# RFM_Sockel.net
KiCad netlist of a schematic drawn in EAGLE
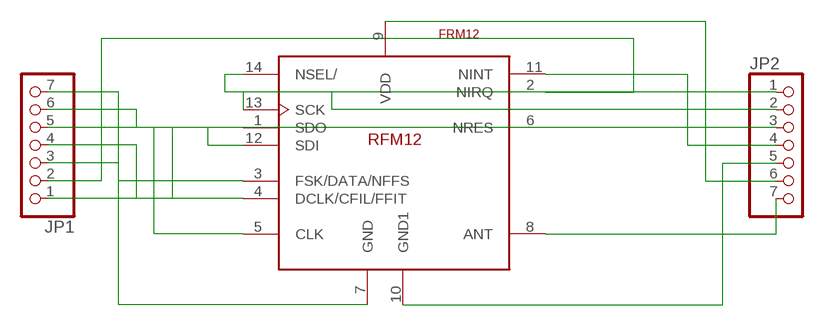
[diagram p0: schematic, sheet 1]

(export (version "E")
  (design (tool "Eeschema 10.0.6"))
  (components
    (comp (ref "JP1")
      (value "PINHD-1X7")
      (footprint "eagle-import:1X07")
      (libsource (lib "eagle-import") (part "PINHD-1X7"))
    )
    (comp (ref "JP2")
      (value "PINHD-1X7")
      (footprint "eagle-import:1X07")
      (libsource (lib "eagle-import") (part "PINHD-1X7"))
    )
    (comp (ref "U$1")
      (value "FRM12")
      (footprint "eagle-import:RFM12")
      (libsource (lib "eagle-import") (part "FRM12"))
    )
  )
  (nets
    (net (code "1") (name "Net-(U$1-ANT)") (class "Default")
      (node (ref "JP2") (pin "7") (pinfunction "7_7") (pintype "passive"))
      (node (ref "U$1") (pin "8") (pinfunction "ANT_8") (pintype "bidirectional"))
    )
    (net (code "2") (name "Net-(U$1-CLK)") (class "Default")
      (node (ref "JP1") (pin "5") (pinfunction "5_5") (pintype "passive"))
      (node (ref "U$1") (pin "5") (pinfunction "CLK_5") (pintype "output"))
    )
    (net (code "3") (name "Net-(U$1-DCLK{slash}CFIL{slash}FFIT)") (class "Default")
      (node (ref "JP1") (pin "4") (pinfunction "4_4") (pintype "passive"))
      (node (ref "U$1") (pin "4") (pinfunction "DCLK/CFIL/FFIT_4") (pintype "bidirectional"))
    )
    (net (code "4") (name "Net-(U$1-FSK{slash}DATA{slash}NFFS)") (class "Default")
      (node (ref "JP1") (pin "3") (pinfunction "3_3") (pintype "passive"))
      (node (ref "U$1") (pin "3") (pinfunction "FSK/DATA/NFFS_3") (pintype "bidirectional"))
    )
    (net (code "5") (name "Net-(U$1-GND)") (class "Default")
      (node (ref "JP1") (pin "7") (pinfunction "7_7") (pintype "passive"))
      (node (ref "U$1") (pin "7") (pinfunction "GND_7") (pintype "passive"))
    )
    (net (code "6") (name "Net-(U$1-GND1)") (class "Default")
      (node (ref "JP2") (pin "5") (pinfunction "5_5") (pintype "passive"))
      (node (ref "U$1") (pin "10") (pinfunction "GND1_10") (pintype "passive"))
    )
    (net (code "7") (name "Net-(U$1-NINT)") (class "Default")
      (node (ref "JP2") (pin "4") (pinfunction "4_4") (pintype "passive"))
      (node (ref "U$1") (pin "11") (pinfunction "NINT_11") (pintype "bidirectional"))
    )
    (net (code "8") (name "Net-(U$1-NIRQ)") (class "Default")
      (node (ref "JP1") (pin "2") (pinfunction "2_2") (pintype "passive"))
      (node (ref "U$1") (pin "2") (pinfunction "NIRQ_2") (pintype "output"))
    )
    (net (code "9") (name "Net-(U$1-NRES)") (class "Default")
      (node (ref "JP1") (pin "6") (pinfunction "6_6") (pintype "passive"))
      (node (ref "U$1") (pin "6") (pinfunction "NRES_6") (pintype "bidirectional"))
    )
    (net (code "10") (name "Net-(U$1-NSEL{slash})") (class "Default")
      (node (ref "JP2") (pin "1") (pinfunction "1_1") (pintype "passive"))
      (node (ref "U$1") (pin "14") (pinfunction "NSEL/_14") (pintype "input"))
    )
    (net (code "11") (name "Net-(U$1-SCK)") (class "Default")
      (node (ref "JP2") (pin "2") (pinfunction "2_2") (pintype "passive"))
      (node (ref "U$1") (pin "13") (pinfunction "SCK_13") (pintype "input"))
    )
    (net (code "12") (name "Net-(U$1-SDI)") (class "Default")
      (node (ref "JP2") (pin "3") (pinfunction "3_3") (pintype "passive"))
      (node (ref "U$1") (pin "12") (pinfunction "SDI_12") (pintype "input"))
    )
    (net (code "13") (name "Net-(U$1-SDO)") (class "Default")
      (node (ref "JP1") (pin "1") (pinfunction "1_1") (pintype "passive"))
      (node (ref "U$1") (pin "1") (pinfunction "SDO_1") (pintype "output"))
    )
    (net (code "14") (name "Net-(U$1-VDD)") (class "Default")
      (node (ref "JP2") (pin "6") (pinfunction "6_6") (pintype "passive"))
      (node (ref "U$1") (pin "9") (pinfunction "VDD_9") (pintype "power_in"))
    )
  )
)
